# nodeconf2018.net
KiCad netlist of a schematic drawn in EAGLE
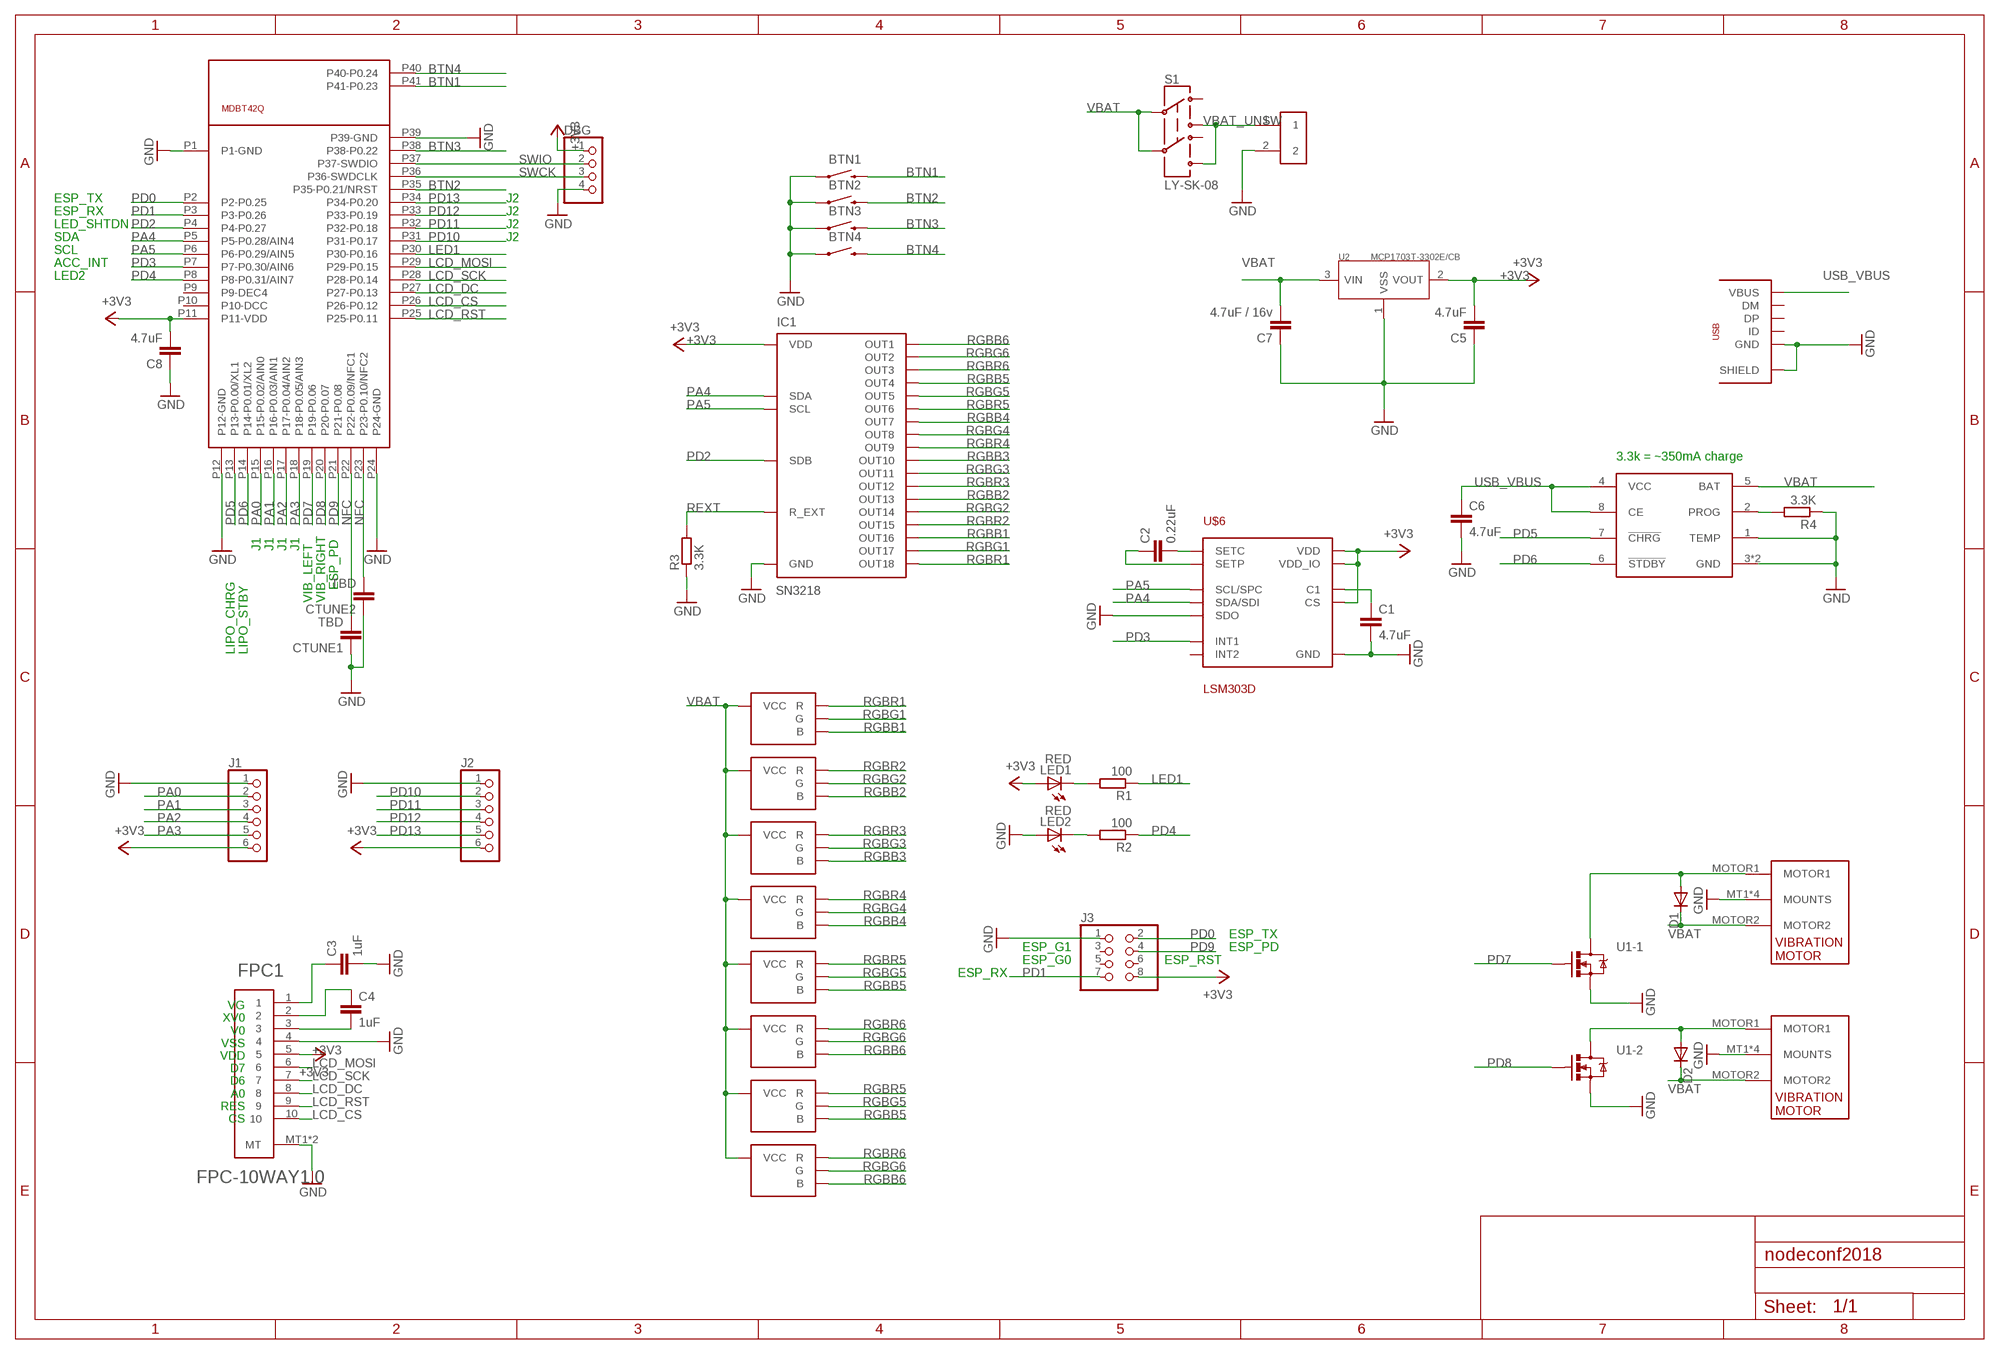
[diagram p0: schematic, sheet 1]

(export (version "E")
  (design (tool "Eeschema 10.0.6"))
  (components
    (comp (ref "BAT")
      (value "JST_2P_VERTICAL")
      (footprint "eagle-import:2P_JST_PH_VERT")
      (libsource (lib "eagle-import") (part "JST_2P_VERTICAL"))
    )
    (comp (ref "BLED1")
      (value "1204RGBC3ADA")
      (footprint "eagle-import:APFA3010SEEZGQBDC")
      (libsource (lib "eagle-import") (part "1204RGBC3ADA"))
    )
    (comp (ref "BLED2")
      (value "1204RGBC3ADA")
      (footprint "eagle-import:APFA3010SEEZGQBDC")
      (libsource (lib "eagle-import") (part "1204RGBC3ADA"))
    )
    (comp (ref "BLED3")
      (value "1204RGBC3ADA")
      (footprint "eagle-import:APFA3010SEEZGQBDC")
      (libsource (lib "eagle-import") (part "1204RGBC3ADA"))
    )
    (comp (ref "BLED4")
      (value "1204RGBC3ADA")
      (footprint "eagle-import:APFA3010SEEZGQBDC")
      (libsource (lib "eagle-import") (part "1204RGBC3ADA"))
    )
    (comp (ref "BLED5")
      (value "1204RGBC3ADA")
      (footprint "eagle-import:APFA3010SEEZGQBDC")
      (libsource (lib "eagle-import") (part "1204RGBC3ADA"))
    )
    (comp (ref "BLED6")
      (value "1204RGBC3ADA")
      (footprint "eagle-import:APFA3010SEEZGQBDC")
      (libsource (lib "eagle-import") (part "1204RGBC3ADA"))
    )
    (comp (ref "BLED7")
      (value "1204RGBC3ADA")
      (footprint "eagle-import:APFA3010SEEZGQBDC")
      (libsource (lib "eagle-import") (part "1204RGBC3ADA"))
    )
    (comp (ref "BLED8")
      (value "1204RGBC3ADA")
      (footprint "eagle-import:APFA3010SEEZGQBDC")
      (libsource (lib "eagle-import") (part "1204RGBC3ADA"))
    )
    (comp (ref "BTN1")
      (value "SWITCH-MOMENTARY-2SMD-1101NE")
      (footprint "eagle-import:TACTILE-SWITCH-1101NE")
      (libsource (lib "eagle-import") (part "SWITCH-MOMENTARY-2SMD-1101NE"))
    )
    (comp (ref "BTN2")
      (value "SWITCH-MOMENTARY-2SMD-1101NE")
      (footprint "eagle-import:TACTILE-SWITCH-1101NE")
      (libsource (lib "eagle-import") (part "SWITCH-MOMENTARY-2SMD-1101NE"))
    )
    (comp (ref "BTN3")
      (value "SWITCH-MOMENTARY-2SMD-1101NE")
      (footprint "eagle-import:TACTILE-SWITCH-1101NE")
      (libsource (lib "eagle-import") (part "SWITCH-MOMENTARY-2SMD-1101NE"))
    )
    (comp (ref "BTN4")
      (value "SWITCH-MOMENTARY-2SMD-1101NE")
      (footprint "eagle-import:TACTILE-SWITCH-1101NE")
      (libsource (lib "eagle-import") (part "SWITCH-MOMENTARY-2SMD-1101NE"))
    )
    (comp (ref "C1")
      (value "4.7uF")
      (footprint "eagle-import:C0805")
      (libsource (lib "eagle-import") (part "C-EUC0805"))
    )
    (comp (ref "C2")
      (value "0.22uF")
      (footprint "eagle-import:C0603K")
      (libsource (lib "eagle-import") (part "C-EUC0603K"))
    )
    (comp (ref "C3")
      (value "1uF")
      (footprint "eagle-import:C0603K")
      (libsource (lib "eagle-import") (part "resistor_C-EUC0603K"))
    )
    (comp (ref "C4")
      (value "1uF")
      (footprint "eagle-import:C0603K")
      (libsource (lib "eagle-import") (part "resistor_C-EUC0603K"))
    )
    (comp (ref "C5")
      (value "4.7uF")
      (footprint "eagle-import:C0805")
      (libsource (lib "eagle-import") (part "C-EUC0805"))
    )
    (comp (ref "C6")
      (value "4.7uF")
      (footprint "eagle-import:C0805")
      (libsource (lib "eagle-import") (part "C-EUC0805"))
    )
    (comp (ref "C7")
      (value "4.7uF / 16v")
      (footprint "eagle-import:C0805")
      (libsource (lib "eagle-import") (part "C-EUC0805"))
    )
    (comp (ref "C8")
      (value "4.7uF")
      (footprint "eagle-import:C0603K")
      (libsource (lib "eagle-import") (part "C-EUC0603K"))
    )
    (comp (ref "CTUNE1")
      (value "TBD")
      (footprint "eagle-import:C0603K")
      (libsource (lib "eagle-import") (part "C-EUC0603K"))
    )
    (comp (ref "CTUNE2")
      (value "TBD")
      (footprint "eagle-import:C0603K")
      (libsource (lib "eagle-import") (part "C-EUC0603K"))
    )
    (comp (ref "D1")
      (value "DIODE-SOD323-W")
      (footprint "eagle-import:SOD323-W")
      (libsource (lib "eagle-import") (part "DIODE-SOD323-W"))
    )
    (comp (ref "D2")
      (value "DIODE-SOD323-W")
      (footprint "eagle-import:SOD323-W")
      (libsource (lib "eagle-import") (part "DIODE-SOD323-W"))
    )
    (comp (ref "DBG")
      (value "PINHD-1X04_2.54-S")
      (footprint "eagle-import:1X04-S")
      (libsource (lib "eagle-import") (part "PINHD-1X04_2.54-S"))
    )
    (comp (ref "FPC1")
      (value "FPC-10WAY1.0")
      (footprint "eagle-import:FPC-1.0MM-10WAY")
      (libsource (lib "eagle-import") (part "FPC-10WAY1.0"))
    )
    (comp (ref "IC1")
      (value "SN3218")
      (footprint "eagle-import:QFN24")
      (libsource (lib "eagle-import") (part "SN3218"))
    )
    (comp (ref "J1")
      (value "PINHD-1X06_2.54-S")
      (footprint "eagle-import:1X06-S")
      (libsource (lib "eagle-import") (part "PINHD-1X06_2.54-S"))
    )
    (comp (ref "J2")
      (value "PINHD-1X06_2.54-S")
      (footprint "eagle-import:1X06-S")
      (libsource (lib "eagle-import") (part "PINHD-1X06_2.54-S"))
    )
    (comp (ref "J3")
      (value "PINHD-2X04_2.54")
      (footprint "eagle-import:2X04")
      (libsource (lib "eagle-import") (part "PINHD-2X04_2.54"))
    )
    (comp (ref "LED1")
      (value "RED")
      (footprint "eagle-import:CHIP-LED0603")
      (libsource (lib "eagle-import") (part "LEDCHIP-LED0603"))
    )
    (comp (ref "LED2")
      (value "RED")
      (footprint "eagle-import:CHIP-LED0603")
      (libsource (lib "eagle-import") (part "LEDCHIP-LED0603"))
    )
    (comp (ref "R1")
      (value "100")
      (footprint "eagle-import:R0603")
      (libsource (lib "eagle-import") (part "R-EU_R0603"))
    )
    (comp (ref "R2")
      (value "100")
      (footprint "eagle-import:R0603")
      (libsource (lib "eagle-import") (part "R-EU_R0603"))
    )
    (comp (ref "R3")
      (value "3.3K")
      (footprint "eagle-import:R0603")
      (libsource (lib "eagle-import") (part "R-EU_R0603"))
    )
    (comp (ref "R4")
      (value "3.3K")
      (footprint "eagle-import:R0603")
      (libsource (lib "eagle-import") (part "R-EU_R0603"))
    )
    (comp (ref "S1")
      (value "LY-SK-08")
      (footprint "eagle-import:SWITCH-DPDT")
      (libsource (lib "eagle-import") (part "SWITCH-DPDT"))
    )
    (comp (ref "U$1")
      (value "VIBRATION_MOTOR")
      (footprint "eagle-import:VIBRATION_MOTOR")
      (libsource (lib "eagle-import") (part "VIBRATION_MOTOR"))
    )
    (comp (ref "U$2")
      (value "VIBRATION_MOTOR")
      (footprint "eagle-import:VIBRATION_MOTOR")
      (libsource (lib "eagle-import") (part "VIBRATION_MOTOR"))
    )
    (comp (ref "U$3")
      (value "MDBT42Q")
      (footprint "eagle-import:MDBT40")
      (libsource (lib "eagle-import") (part "MDBT42Q"))
    )
    (comp (ref "U$4")
      (value "USBMICROB")
      (footprint "eagle-import:MICROB-USB")
      (libsource (lib "eagle-import") (part "USBMICROB"))
    )
    (comp (ref "U$6")
      (value "LSM303D")
      (footprint "eagle-import:LGA16-3MM")
      (libsource (lib "eagle-import") (part "LSM303D"))
    )
    (comp (ref "U1")
      (value "MOSFET-N-DUAL")
      (footprint "eagle-import:SOT563")
      (libsource (lib "eagle-import") (part "MOSFET-N-DUAL"))
    )
    (comp (ref "U2")
      (value "MCP1703T-3302E/CB")
      (footprint "eagle-import:SOT23")
      (libsource (lib "eagle-import") (part "XC6206"))
    )
    (comp (ref "U3")
      (value "TP4056")
      (footprint "eagle-import:SO08-PAD-300")
      (libsource (lib "eagle-import") (part "TP4056"))
    )
  )
  (nets
    (net (code "1") (name "+3V3") (class "Default")
      (node (ref "C5") (pin "2") (pinfunction "2_2") (pintype "passive"))
      (node (ref "C8") (pin "2") (pinfunction "2_2") (pintype "passive"))
      (node (ref "DBG") (pin "1") (pinfunction "1_1") (pintype "passive"))
      (node (ref "FPC1") (pin "5") (pinfunction "5_5") (pintype "bidirectional"))
      (node (ref "IC1") (pin "3") (pinfunction "VDD_3") (pintype "bidirectional"))
      (node (ref "J1") (pin "6") (pinfunction "6_6") (pintype "passive"))
      (node (ref "J2") (pin "6") (pinfunction "6_6") (pintype "passive"))
      (node (ref "J3") (pin "8") (pinfunction "8_8") (pintype "passive"))
      (node (ref "LED1") (pin "A") (pinfunction "A_A") (pintype "passive"))
      (node (ref "U$3") (pin "P11") (pinfunction "P11-VDD_P11") (pintype "bidirectional"))
      (node (ref "U$6") (pin "1") (pinfunction "VDD_IO_1") (pintype "power_in"))
      (node (ref "U$6") (pin "14") (pinfunction "VDD_14") (pintype "bidirectional"))
      (node (ref "U$6") (pin "8") (pinfunction "CS_8") (pintype "bidirectional"))
      (node (ref "U2") (pin "2") (pinfunction "VOUT_2") (pintype "output"))
    )
    (net (code "2") (name "/BTN1") (class "Default")
      (node (ref "BTN1") (pin "2") (pinfunction "2_2") (pintype "passive"))
      (node (ref "U$3") (pin "P41") (pinfunction "P41-P0.23_P41") (pintype "bidirectional"))
    )
    (net (code "3") (name "/BTN2") (class "Default")
      (node (ref "BTN2") (pin "2") (pinfunction "2_2") (pintype "passive"))
      (node (ref "U$3") (pin "P35") (pinfunction "P35-P0.21/NRST_P35") (pintype "bidirectional"))
    )
    (net (code "4") (name "/BTN3") (class "Default")
      (node (ref "BTN3") (pin "2") (pinfunction "2_2") (pintype "passive"))
      (node (ref "U$3") (pin "P38") (pinfunction "P38-P0.22_P38") (pintype "bidirectional"))
    )
    (net (code "5") (name "/BTN4") (class "Default")
      (node (ref "BTN4") (pin "2") (pinfunction "2_2") (pintype "passive"))
      (node (ref "U$3") (pin "P40") (pinfunction "P40-P0.24_P40") (pintype "bidirectional"))
    )
    (net (code "6") (name "/LCD_CS") (class "Default")
      (node (ref "FPC1") (pin "10") (pinfunction "10_10") (pintype "bidirectional"))
      (node (ref "U$3") (pin "P26") (pinfunction "P26-P0.12_P26") (pintype "bidirectional"))
    )
    (net (code "7") (name "/LCD_DC") (class "Default")
      (node (ref "FPC1") (pin "8") (pinfunction "8_8") (pintype "bidirectional"))
      (node (ref "U$3") (pin "P27") (pinfunction "P27-P0.13_P27") (pintype "bidirectional"))
    )
    (net (code "8") (name "/LCD_MOSI") (class "Default")
      (node (ref "FPC1") (pin "6") (pinfunction "6_6") (pintype "bidirectional"))
      (node (ref "U$3") (pin "P29") (pinfunction "P29-P0.15_P29") (pintype "bidirectional"))
    )
    (net (code "9") (name "/LCD_RST") (class "Default")
      (node (ref "FPC1") (pin "9") (pinfunction "9_9") (pintype "bidirectional"))
      (node (ref "U$3") (pin "P25") (pinfunction "P25-P0.11_P25") (pintype "bidirectional"))
    )
    (net (code "10") (name "/LCD_SCK") (class "Default")
      (node (ref "FPC1") (pin "7") (pinfunction "7_7") (pintype "bidirectional"))
      (node (ref "U$3") (pin "P28") (pinfunction "P28-P0.14_P28") (pintype "bidirectional"))
    )
    (net (code "11") (name "/LED1") (class "Default")
      (node (ref "R1") (pin "1") (pinfunction "1_1") (pintype "passive"))
      (node (ref "U$3") (pin "P30") (pinfunction "P30-P0.16_P30") (pintype "bidirectional"))
    )
    (net (code "12") (name "/NFC") (class "Default")
      (node (ref "CTUNE1") (pin "2") (pinfunction "2_2") (pintype "passive"))
      (node (ref "CTUNE2") (pin "2") (pinfunction "2_2") (pintype "passive"))
      (node (ref "U$3") (pin "P22") (pinfunction "P22-P0.09/NFC1_P22") (pintype "bidirectional"))
      (node (ref "U$3") (pin "P23") (pinfunction "P23-P0.10/NFC2_P23") (pintype "bidirectional"))
    )
    (net (code "13") (name "/PA0") (class "Default")
      (node (ref "J1") (pin "2") (pinfunction "2_2") (pintype "passive"))
      (node (ref "U$3") (pin "P15") (pinfunction "P15-P0.02/AIN0_P15") (pintype "bidirectional"))
    )
    (net (code "14") (name "/PA1") (class "Default")
      (node (ref "J1") (pin "3") (pinfunction "3_3") (pintype "passive"))
      (node (ref "U$3") (pin "P16") (pinfunction "P16-P0.03/AIN1_P16") (pintype "bidirectional"))
    )
    (net (code "15") (name "/PA2") (class "Default")
      (node (ref "J1") (pin "4") (pinfunction "4_4") (pintype "passive"))
      (node (ref "U$3") (pin "P17") (pinfunction "P17-P0.04/AIN2_P17") (pintype "bidirectional"))
    )
    (net (code "16") (name "/PA3") (class "Default")
      (node (ref "J1") (pin "5") (pinfunction "5_5") (pintype "passive"))
      (node (ref "U$3") (pin "P18") (pinfunction "P18-P0.05/AIN3_P18") (pintype "bidirectional"))
    )
    (net (code "17") (name "/PA4") (class "Default")
      (node (ref "IC1") (pin "5") (pinfunction "SDA_5") (pintype "bidirectional"))
      (node (ref "U$3") (pin "P5") (pinfunction "P5-P0.28/AIN4_P5") (pintype "bidirectional"))
      (node (ref "U$6") (pin "6") (pinfunction "SDA/SDI_6") (pintype "bidirectional"))
    )
    (net (code "18") (name "/PA5") (class "Default")
      (node (ref "IC1") (pin "6") (pinfunction "SCL_6") (pintype "bidirectional"))
      (node (ref "U$3") (pin "P6") (pinfunction "P6-P0.29/AIN5_P6") (pintype "bidirectional"))
      (node (ref "U$6") (pin "4") (pinfunction "SCL/SPC_4") (pintype "bidirectional"))
    )
    (net (code "19") (name "/PD0") (class "Default")
      (node (ref "J3") (pin "2") (pinfunction "2_2") (pintype "passive"))
      (node (ref "U$3") (pin "P2") (pinfunction "P2-P0.25_P2") (pintype "bidirectional"))
    )
    (net (code "20") (name "/PD1") (class "Default")
      (node (ref "J3") (pin "7") (pinfunction "7_7") (pintype "passive"))
      (node (ref "U$3") (pin "P3") (pinfunction "P3-P0.26_P3") (pintype "bidirectional"))
    )
    (net (code "21") (name "/PD2") (class "Default")
      (node (ref "IC1") (pin "24") (pinfunction "SDB_24") (pintype "bidirectional"))
      (node (ref "U$3") (pin "P4") (pinfunction "P4-P0.27_P4") (pintype "bidirectional"))
    )
    (net (code "22") (name "/PD3") (class "Default")
      (node (ref "U$3") (pin "P7") (pinfunction "P7-P0.30/AIN6_P7") (pintype "bidirectional"))
      (node (ref "U$6") (pin "11") (pinfunction "INT1_11") (pintype "bidirectional"))
    )
    (net (code "23") (name "/PD4") (class "Default")
      (node (ref "R2") (pin "1") (pinfunction "1_1") (pintype "passive"))
      (node (ref "U$3") (pin "P8") (pinfunction "P8-P0.31/AIN7_P8") (pintype "bidirectional"))
    )
    (net (code "24") (name "/PD5") (class "Default")
      (node (ref "U$3") (pin "P13") (pinfunction "P13-P0.00/XL1_P13") (pintype "bidirectional"))
      (node (ref "U3") (pin "7") (pinfunction "~{CHRG}_7") (pintype "bidirectional"))
    )
    (net (code "25") (name "/PD6") (class "Default")
      (node (ref "U$3") (pin "P14") (pinfunction "P14-P0.01/XL2_P14") (pintype "bidirectional"))
      (node (ref "U3") (pin "6") (pinfunction "~{STDBY}_6") (pintype "bidirectional"))
    )
    (net (code "26") (name "/PD7") (class "Default")
      (node (ref "U$3") (pin "P19") (pinfunction "P19-P0.06_P19") (pintype "bidirectional"))
      (node (ref "U1") (pin "G1") (pinfunction "G_G1") (pintype "passive"))
    )
    (net (code "27") (name "/PD8") (class "Default")
      (node (ref "U$3") (pin "P20") (pinfunction "P20-P0.07_P20") (pintype "bidirectional"))
      (node (ref "U1") (pin "G2") (pinfunction "G_G2") (pintype "passive"))
    )
    (net (code "28") (name "/PD9") (class "Default")
      (node (ref "J3") (pin "4") (pinfunction "4_4") (pintype "passive"))
      (node (ref "U$3") (pin "P21") (pinfunction "P21-P0.08_P21") (pintype "bidirectional"))
    )
    (net (code "29") (name "/PD10") (class "Default")
      (node (ref "J2") (pin "2") (pinfunction "2_2") (pintype "passive"))
      (node (ref "U$3") (pin "P31") (pinfunction "P31-P0.17_P31") (pintype "bidirectional"))
    )
    (net (code "30") (name "/PD11") (class "Default")
      (node (ref "J2") (pin "3") (pinfunction "3_3") (pintype "passive"))
      (node (ref "U$3") (pin "P32") (pinfunction "P32-P0.18_P32") (pintype "bidirectional"))
    )
    (net (code "31") (name "/PD12") (class "Default")
      (node (ref "J2") (pin "4") (pinfunction "4_4") (pintype "passive"))
      (node (ref "U$3") (pin "P33") (pinfunction "P33-P0.19_P33") (pintype "bidirectional"))
    )
    (net (code "32") (name "/PD13") (class "Default")
      (node (ref "J2") (pin "5") (pinfunction "5_5") (pintype "passive"))
      (node (ref "U$3") (pin "P34") (pinfunction "P34-P0.20_P34") (pintype "bidirectional"))
    )
    (net (code "33") (name "/REXT") (class "Default")
      (node (ref "IC1") (pin "2") (pinfunction "R_EXT_2") (pintype "bidirectional"))
      (node (ref "R3") (pin "2") (pinfunction "2_2") (pintype "passive"))
    )
    (net (code "34") (name "/RGBB1") (class "Default")
      (node (ref "BLED1") (pin "2") (pinfunction "B_2") (pintype "bidirectional"))
      (node (ref "IC1") (pin "22") (pinfunction "OUT16_22") (pintype "bidirectional"))
    )
    (net (code "35") (name "/RGBB2") (class "Default")
      (node (ref "BLED2") (pin "2") (pinfunction "B_2") (pintype "bidirectional"))
      (node (ref "IC1") (pin "19") (pinfunction "OUT13_19") (pintype "bidirectional"))
    )
    (net (code "36") (name "/RGBB3") (class "Default")
      (node (ref "BLED3") (pin "2") (pinfunction "B_2") (pintype "bidirectional"))
      (node (ref "IC1") (pin "16") (pinfunction "OUT10_16") (pintype "bidirectional"))
    )
    (net (code "37") (name "/RGBB4") (class "Default")
      (node (ref "BLED4") (pin "2") (pinfunction "B_2") (pintype "bidirectional"))
      (node (ref "IC1") (pin "13") (pinfunction "OUT7_13") (pintype "bidirectional"))
    )
    (net (code "38") (name "/RGBB5") (class "Default")
      (node (ref "BLED5") (pin "2") (pinfunction "B_2") (pintype "bidirectional"))
      (node (ref "BLED7") (pin "2") (pinfunction "B_2") (pintype "bidirectional"))
      (node (ref "IC1") (pin "10") (pinfunction "OUT4_10") (pintype "bidirectional"))
    )
    (net (code "39") (name "/RGBB6") (class "Default")
      (node (ref "BLED6") (pin "2") (pinfunction "B_2") (pintype "bidirectional"))
      (node (ref "BLED8") (pin "2") (pinfunction "B_2") (pintype "bidirectional"))
      (node (ref "IC1") (pin "7") (pinfunction "OUT1_7") (pintype "bidirectional"))
    )
    (net (code "40") (name "/RGBG1") (class "Default")
      (node (ref "BLED1") (pin "1") (pinfunction "G_1") (pintype "bidirectional"))
      (node (ref "IC1") (pin "23") (pinfunction "OUT17_23") (pintype "bidirectional"))
    )
    (net (code "41") (name "/RGBG2") (class "Default")
      (node (ref "BLED2") (pin "1") (pinfunction "G_1") (pintype "bidirectional"))
      (node (ref "IC1") (pin "20") (pinfunction "OUT14_20") (pintype "bidirectional"))
    )
    (net (code "42") (name "/RGBG3") (class "Default")
      (node (ref "BLED3") (pin "1") (pinfunction "G_1") (pintype "bidirectional"))
      (node (ref "IC1") (pin "17") (pinfunction "OUT11_17") (pintype "bidirectional"))
    )
    (net (code "43") (name "/RGBG4") (class "Default")
      (node (ref "BLED4") (pin "1") (pinfunction "G_1") (pintype "bidirectional"))
      (node (ref "IC1") (pin "14") (pinfunction "OUT8_14") (pintype "bidirectional"))
    )
    (net (code "44") (name "/RGBG5") (class "Default")
      (node (ref "BLED5") (pin "1") (pinfunction "G_1") (pintype "bidirectional"))
      (node (ref "BLED7") (pin "1") (pinfunction "G_1") (pintype "bidirectional"))
      (node (ref "IC1") (pin "11") (pinfunction "OUT5_11") (pintype "bidirectional"))
    )
    (net (code "45") (name "/RGBG6") (class "Default")
      (node (ref "BLED6") (pin "1") (pinfunction "G_1") (pintype "bidirectional"))
      (node (ref "BLED8") (pin "1") (pinfunction "G_1") (pintype "bidirectional"))
      (node (ref "IC1") (pin "8") (pinfunction "OUT2_8") (pintype "bidirectional"))
    )
    (net (code "46") (name "/RGBR1") (class "Default")
      (node (ref "BLED1") (pin "3") (pinfunction "R_3") (pintype "bidirectional"))
      (node (ref "IC1") (pin "1") (pinfunction "OUT18_1") (pintype "bidirectional"))
    )
    (net (code "47") (name "/RGBR2") (class "Default")
      (node (ref "BLED2") (pin "3") (pinfunction "R_3") (pintype "bidirectional"))
      (node (ref "IC1") (pin "21") (pinfunction "OUT15_21") (pintype "bidirectional"))
    )
    (net (code "48") (name "/RGBR3") (class "Default")
      (node (ref "BLED3") (pin "3") (pinfunction "R_3") (pintype "bidirectional"))
      (node (ref "IC1") (pin "18") (pinfunction "OUT12_18") (pintype "bidirectional"))
    )
    (net (code "49") (name "/RGBR4") (class "Default")
      (node (ref "BLED4") (pin "3") (pinfunction "R_3") (pintype "bidirectional"))
      (node (ref "IC1") (pin "15") (pinfunction "OUT9_15") (pintype "bidirectional"))
    )
    (net (code "50") (name "/RGBR5") (class "Default")
      (node (ref "BLED5") (pin "3") (pinfunction "R_3") (pintype "bidirectional"))
      (node (ref "BLED7") (pin "3") (pinfunction "R_3") (pintype "bidirectional"))
      (node (ref "IC1") (pin "12") (pinfunction "OUT6_12") (pintype "bidirectional"))
    )
    (net (code "51") (name "/RGBR6") (class "Default")
      (node (ref "BLED6") (pin "3") (pinfunction "R_3") (pintype "bidirectional"))
      (node (ref "BLED8") (pin "3") (pinfunction "R_3") (pintype "bidirectional"))
      (node (ref "IC1") (pin "9") (pinfunction "OUT3_9") (pintype "bidirectional"))
    )
    (net (code "52") (name "/SWCK") (class "Default")
      (node (ref "DBG") (pin "3") (pinfunction "3_3") (pintype "passive"))
      (node (ref "U$3") (pin "P36") (pinfunction "P36-SWDCLK_P36") (pintype "bidirectional"))
    )
    (net (code "53") (name "/SWIO") (class "Default")
      (node (ref "DBG") (pin "2") (pinfunction "2_2") (pintype "passive"))
      (node (ref "U$3") (pin "P37") (pinfunction "P37-SWDIO_P37") (pintype "bidirectional"))
    )
    (net (code "54") (name "/USB_VBUS") (class "Default")
      (node (ref "C6") (pin "1") (pinfunction "1_1") (pintype "passive"))
      (node (ref "U$4") (pin "VBUS") (pinfunction "VBUS_VBUS") (pintype "bidirectional"))
      (node (ref "U3") (pin "4") (pinfunction "VCC_4") (pintype "bidirectional"))
      (node (ref "U3") (pin "8") (pinfunction "CE_8") (pintype "bidirectional"))
    )
    (net (code "55") (name "/VBAT") (class "Default")
      (node (ref "BLED1") (pin "4") (pinfunction "VCC_4") (pintype "bidirectional"))
      (node (ref "BLED2") (pin "4") (pinfunction "VCC_4") (pintype "bidirectional"))
      (node (ref "BLED3") (pin "4") (pinfunction "VCC_4") (pintype "bidirectional"))
      (node (ref "BLED4") (pin "4") (pinfunction "VCC_4") (pintype "bidirectional"))
      (node (ref "BLED5") (pin "4") (pinfunction "VCC_4") (pintype "bidirectional"))
      (node (ref "BLED6") (pin "4") (pinfunction "VCC_4") (pintype "bidirectional"))
      (node (ref "BLED7") (pin "4") (pinfunction "VCC_4") (pintype "bidirectional"))
      (node (ref "BLED8") (pin "4") (pinfunction "VCC_4") (pintype "bidirectional"))
      (node (ref "C7") (pin "2") (pinfunction "2_2") (pintype "passive"))
      (node (ref "D1") (pin "C") (pinfunction "C_C") (pintype "passive"))
      (node (ref "D2") (pin "C") (pinfunction "C_C") (pintype "passive"))
      (node (ref "S1") (pin "2") (pinfunction "A_P_2") (pintype "bidirectional"))
      (node (ref "S1") (pin "5") (pinfunction "B_P_5") (pintype "bidirectional"))
      (node (ref "U$1") (pin "MOTOR2") (pinfunction "MOTOR2_MOTOR2") (pintype "bidirectional"))
      (node (ref "U$2") (pin "MOTOR2") (pinfunction "MOTOR2_MOTOR2") (pintype "bidirectional"))
      (node (ref "U2") (pin "3") (pinfunction "VIN_3") (pintype "input"))
      (node (ref "U3") (pin "5") (pinfunction "BAT_5") (pintype "bidirectional"))
    )
    (net (code "56") (name "/VBAT_UNSW") (class "Default")
      (node (ref "BAT") (pin "1") (pinfunction "1_1") (pintype "bidirectional"))
      (node (ref "S1") (pin "1") (pinfunction "A_T2_1") (pintype "bidirectional"))
      (node (ref "S1") (pin "6") (pinfunction "B_T2_6") (pintype "bidirectional"))
    )
    (net (code "57") (name "GND") (class "Default")
      (node (ref "BAT") (pin "2") (pinfunction "2_2") (pintype "bidirectional"))
      (node (ref "BTN1") (pin "1") (pinfunction "1_1") (pintype "passive"))
      (node (ref "BTN2") (pin "1") (pinfunction "1_1") (pintype "passive"))
      (node (ref "BTN3") (pin "1") (pinfunction "1_1") (pintype "passive"))
      (node (ref "BTN4") (pin "1") (pinfunction "1_1") (pintype "passive"))
      (node (ref "C1") (pin "2") (pinfunction "2_2") (pintype "passive"))
      (node (ref "C3") (pin "2") (pinfunction "2_2") (pintype "passive"))
      (node (ref "C5") (pin "1") (pinfunction "1_1") (pintype "passive"))
      (node (ref "C6") (pin "2") (pinfunction "2_2") (pintype "passive"))
      (node (ref "C7") (pin "1") (pinfunction "1_1") (pintype "passive"))
      (node (ref "C8") (pin "1") (pinfunction "1_1") (pintype "passive"))
      (node (ref "CTUNE1") (pin "1") (pinfunction "1_1") (pintype "passive"))
      (node (ref "CTUNE2") (pin "1") (pinfunction "1_1") (pintype "passive"))
      (node (ref "DBG") (pin "4") (pinfunction "4_4") (pintype "passive"))
      (node (ref "FPC1") (pin "4") (pinfunction "4_4") (pintype "bidirectional"))
      (node (ref "FPC1") (pin "MT1") (pinfunction "MT_MT1") (pintype "bidirectional"))
      (node (ref "FPC1") (pin "MT2") (pinfunction "MT_MT2") (pintype "bidirectional"))
      (node (ref "IC1") (pin "4") (pinfunction "GND_4") (pintype "bidirectional"))
      (node (ref "IC1") (pin "GND") (pinfunction "GND_GND") (pintype "bidirectional"))
      (node (ref "J1") (pin "1") (pinfunction "1_1") (pintype "passive"))
      (node (ref "J2") (pin "1") (pinfunction "1_1") (pintype "passive"))
      (node (ref "J3") (pin "1") (pinfunction "1_1") (pintype "passive"))
      (node (ref "LED2") (pin "A") (pinfunction "A_A") (pintype "passive"))
      (node (ref "R3") (pin "1") (pinfunction "1_1") (pintype "passive"))
      (node (ref "R4") (pin "1") (pinfunction "1_1") (pintype "passive"))
      (node (ref "U$1") (pin "MT1") (pinfunction "MOUNTS_MT1") (pintype "bidirectional"))
      (node (ref "U$1") (pin "MT2") (pinfunction "MOUNTS_MT2") (pintype "bidirectional"))
      (node (ref "U$1") (pin "MT3") (pinfunction "MOUNTS_MT3") (pintype "bidirectional"))
      (node (ref "U$1") (pin "MT4") (pinfunction "MOUNTS_MT4") (pintype "bidirectional"))
      (node (ref "U$2") (pin "MT1") (pinfunction "MOUNTS_MT1") (pintype "bidirectional"))
      (node (ref "U$2") (pin "MT2") (pinfunction "MOUNTS_MT2") (pintype "bidirectional"))
      (node (ref "U$2") (pin "MT3") (pinfunction "MOUNTS_MT3") (pintype "bidirectional"))
      (node (ref "U$2") (pin "MT4") (pinfunction "MOUNTS_MT4") (pintype "bidirectional"))
      (node (ref "U$3") (pin "P1") (pinfunction "P1-GND_P1") (pintype "bidirectional"))
      (node (ref "U$3") (pin "P12") (pinfunction "P12-GND_P12") (pintype "bidirectional"))
      (node (ref "U$3") (pin "P24") (pinfunction "P24-GND_P24") (pintype "bidirectional"))
      (node (ref "U$3") (pin "P39") (pinfunction "P39-GND_P39") (pintype "bidirectional"))
      (node (ref "U$4") (pin "GND") (pinfunction "GND_GND") (pintype "bidirectional"))
      (node (ref "U$4") (pin "SH1") (pinfunction "SHIELD_SH1") (pintype "bidirectional"))
      (node (ref "U$4") (pin "SH2") (pinfunction "SHIELD_SH2") (pintype "bidirectional"))
      (node (ref "U$4") (pin "SH3") (pinfunction "SHIELD_SH3") (pintype "bidirectional"))
      (node (ref "U$4") (pin "SH4") (pinfunction "SHIELD_SH4") (pintype "bidirectional"))
      (node (ref "U$4") (pin "SH5") (pinfunction "SHIELD_SH5") (pintype "bidirectional"))
      (node (ref "U$4") (pin "SH6") (pinfunction "SHIELD_SH6") (pintype "bidirectional"))
      (node (ref "U$4") (pin "SH7") (pinfunction "SHIELD_SH7") (pintype "bidirectional"))
      (node (ref "U$4") (pin "SH8") (pinfunction "SHIELD_SH8") (pintype "bidirectional"))
      (node (ref "U$6") (pin "10") (pinfunction "GND_10") (pintype "power_in"))
      (node (ref "U$6") (pin "12") (pinfunction "GND_12") (pintype "power_in"))
      (node (ref "U$6") (pin "13") (pinfunction "GND_13") (pintype "power_in"))
      (node (ref "U$6") (pin "16") (pinfunction "GND_16") (pintype "power_in"))
      (node (ref "U$6") (pin "5") (pinfunction "GND_5") (pintype "power_in"))
      (node (ref "U$6") (pin "7") (pinfunction "SDO_7") (pintype "bidirectional"))
      (node (ref "U1") (pin "S1") (pinfunction "S_S1") (pintype "passive"))
      (node (ref "U1") (pin "S2") (pinfunction "S_S2") (pintype "passive"))
      (node (ref "U2") (pin "1") (pinfunction "VSS_1") (pintype "power_in"))
      (node (ref "U3") (pin "1") (pinfunction "TEMP_1") (pintype "bidirectional"))
      (node (ref "U3") (pin "3") (pinfunction "GND_3") (pintype "bidirectional"))
      (node (ref "U3") (pin "PAD") (pinfunction "GND_PAD") (pintype "bidirectional"))
    )
    (net (code "58") (name "Net-(C3-Pad1)") (class "Default")
      (node (ref "C3") (pin "1") (pinfunction "1_1") (pintype "passive"))
      (node (ref "FPC1") (pin "1") (pinfunction "1_1") (pintype "bidirectional"))
    )
    (net (code "59") (name "Net-(C4-Pad1)") (class "Default")
      (node (ref "C4") (pin "1") (pinfunction "1_1") (pintype "passive"))
      (node (ref "FPC1") (pin "2") (pinfunction "2_2") (pintype "bidirectional"))
    )
    (net (code "60") (name "Net-(C4-Pad2)") (class "Default")
      (node (ref "C4") (pin "2") (pinfunction "2_2") (pintype "passive"))
      (node (ref "FPC1") (pin "3") (pinfunction "3_3") (pintype "bidirectional"))
    )
    (net (code "61") (name "Net-(LED1-PadC)") (class "Default")
      (node (ref "LED1") (pin "C") (pinfunction "C_C") (pintype "passive"))
      (node (ref "R1") (pin "2") (pinfunction "2_2") (pintype "passive"))
    )
    (net (code "62") (name "Net-(LED2-PadC)") (class "Default")
      (node (ref "LED2") (pin "C") (pinfunction "C_C") (pintype "passive"))
      (node (ref "R2") (pin "2") (pinfunction "2_2") (pintype "passive"))
    )
    (net (code "63") (name "Net-(U$6-C1)") (class "Default")
      (node (ref "C1") (pin "1") (pinfunction "1_1") (pintype "passive"))
      (node (ref "U$6") (pin "15") (pinfunction "C1_15") (pintype "bidirectional"))
    )
    (net (code "64") (name "Net-(U$6-SETC)") (class "Default")
      (node (ref "C2") (pin "2") (pinfunction "2_2") (pintype "passive"))
      (node (ref "U$6") (pin "2") (pinfunction "SETC_2") (pintype "bidirectional"))
    )
    (net (code "65") (name "Net-(U$6-SETP)") (class "Default")
      (node (ref "C2") (pin "1") (pinfunction "1_1") (pintype "passive"))
      (node (ref "U$6") (pin "3") (pinfunction "SETP_3") (pintype "bidirectional"))
    )
    (net (code "66") (name "Net-(U1A-D)") (class "Default")
      (node (ref "D1") (pin "A") (pinfunction "A_A") (pintype "passive"))
      (node (ref "U$1") (pin "MOTOR1") (pinfunction "MOTOR1_MOTOR1") (pintype "bidirectional"))
      (node (ref "U1") (pin "D1") (pinfunction "D_D1") (pintype "passive"))
    )
    (net (code "67") (name "Net-(U1B-D)") (class "Default")
      (node (ref "D2") (pin "A") (pinfunction "A_A") (pintype "passive"))
      (node (ref "U$2") (pin "MOTOR1") (pinfunction "MOTOR1_MOTOR1") (pintype "bidirectional"))
      (node (ref "U1") (pin "D2") (pinfunction "D_D2") (pintype "passive"))
    )
    (net (code "68") (name "Net-(U3-PROG)") (class "Default")
      (node (ref "R4") (pin "2") (pinfunction "2_2") (pintype "passive"))
      (node (ref "U3") (pin "2") (pinfunction "PROG_2") (pintype "bidirectional"))
    )
    (net (code "69") (name "unconnected-(J3-Pad3)") (class "Default")
      (node (ref "J3") (pin "3") (pinfunction "3_3") (pintype "passive"))
    )
    (net (code "70") (name "unconnected-(J3-Pad5)") (class "Default")
      (node (ref "J3") (pin "5") (pinfunction "5_5") (pintype "passive"))
    )
    (net (code "71") (name "unconnected-(J3-Pad6)") (class "Default")
      (node (ref "J3") (pin "6") (pinfunction "6_6") (pintype "passive"))
    )
    (net (code "72") (name "unconnected-(S1-A_T1-Pad3)") (class "Default")
      (node (ref "S1") (pin "3") (pinfunction "A_T1_3") (pintype "bidirectional"))
    )
    (net (code "73") (name "unconnected-(S1-B_T1-Pad4)") (class "Default")
      (node (ref "S1") (pin "4") (pinfunction "B_T1_4") (pintype "bidirectional"))
    )
    (net (code "74") (name "unconnected-(U$3-P9-DEC4-PadP9)") (class "Default")
      (node (ref "U$3") (pin "P9") (pinfunction "P9-DEC4_P9") (pintype "bidirectional"))
    )
    (net (code "75") (name "unconnected-(U$3-P10-DCC-PadP10)") (class "Default")
      (node (ref "U$3") (pin "P10") (pinfunction "P10-DCC_P10") (pintype "bidirectional"))
    )
    (net (code "76") (name "unconnected-(U$4-PadDM)") (class "Default")
      (node (ref "U$4") (pin "DM") (pinfunction "DM_DM") (pintype "bidirectional"))
    )
    (net (code "77") (name "unconnected-(U$4-PadDP)") (class "Default")
      (node (ref "U$4") (pin "DP") (pinfunction "DP_DP") (pintype "bidirectional"))
    )
    (net (code "78") (name "unconnected-(U$4-PadID)") (class "Default")
      (node (ref "U$4") (pin "ID") (pinfunction "ID_ID") (pintype "bidirectional"))
    )
    (net (code "79") (name "unconnected-(U$6-INT2-Pad9)") (class "Default")
      (node (ref "U$6") (pin "9") (pinfunction "INT2_9") (pintype "bidirectional"))
    )
  )
)
